# LED.net
KiCad netlist of a schematic drawn in Altium Designer
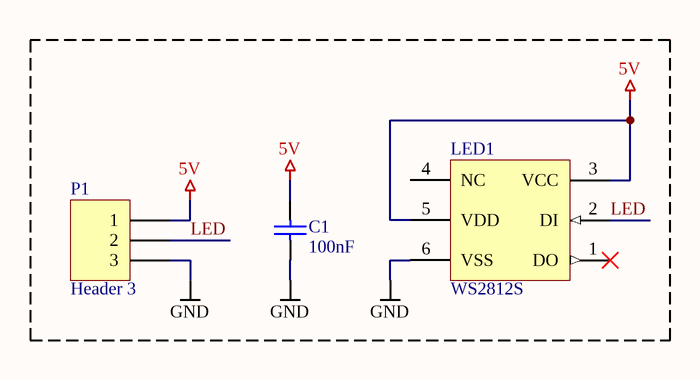
[diagram p0: LED.SchDoc]

(export (version "E")
  (design (tool "Eeschema 10.0.6"))
  (components
    (comp (ref "C1")
      (value "100nF")
      (footprint "C0805")
      (description "Capacitor")
      (libsource (lib "Library") (part "Cap"))
    )
    (comp (ref "LED1") (value "WS2812S") (footprint "WS2812") (libsource (lib "Library") (part "WS2812")))
    (comp (ref "P1")
      (value "Header 3")
      (footprint "MA03-1L")
      (description "Header, 3-Pin")
      (libsource (lib "Connectors") (part "Header 3"))
    )
  )
  (nets
    (net (code "1") (name "/LED") (class "Default")
      (node (ref "LED1") (pin "2") (pinfunction "DI_2") (pintype "input"))
      (node (ref "P1") (pin "2") (pinfunction "2_2") (pintype "passive"))
    )
    (net (code "2") (name "5V") (class "Default")
      (node (ref "C1") (pin "1") (pinfunction "1_1") (pintype "passive"))
      (node (ref "LED1") (pin "3") (pinfunction "VCC_3") (pintype "power_in"))
      (node (ref "LED1") (pin "5") (pinfunction "VDD_5") (pintype "power_in"))
      (node (ref "P1") (pin "1") (pinfunction "1_1") (pintype "passive"))
    )
    (net (code "3") (name "GND") (class "Default")
      (node (ref "C1") (pin "2") (pinfunction "2_2") (pintype "passive"))
      (node (ref "LED1") (pin "6") (pinfunction "VSS_6") (pintype "power_in"))
      (node (ref "P1") (pin "3") (pinfunction "3_3") (pintype "passive"))
    )
    (net (code "4") (name "unconnected-(LED1-DO-Pad1)") (class "Default")
      (node (ref "LED1") (pin "1") (pinfunction "DO_1") (pintype "output+no_connect"))
    )
    (net (code "5") (name "unconnected-(LED1-NC-Pad4)") (class "Default")
      (node (ref "LED1") (pin "4") (pinfunction "NC_4") (pintype "passive"))
    )
  )
)
